# spinac.net
KiCad netlist of a schematic drawn in EAGLE
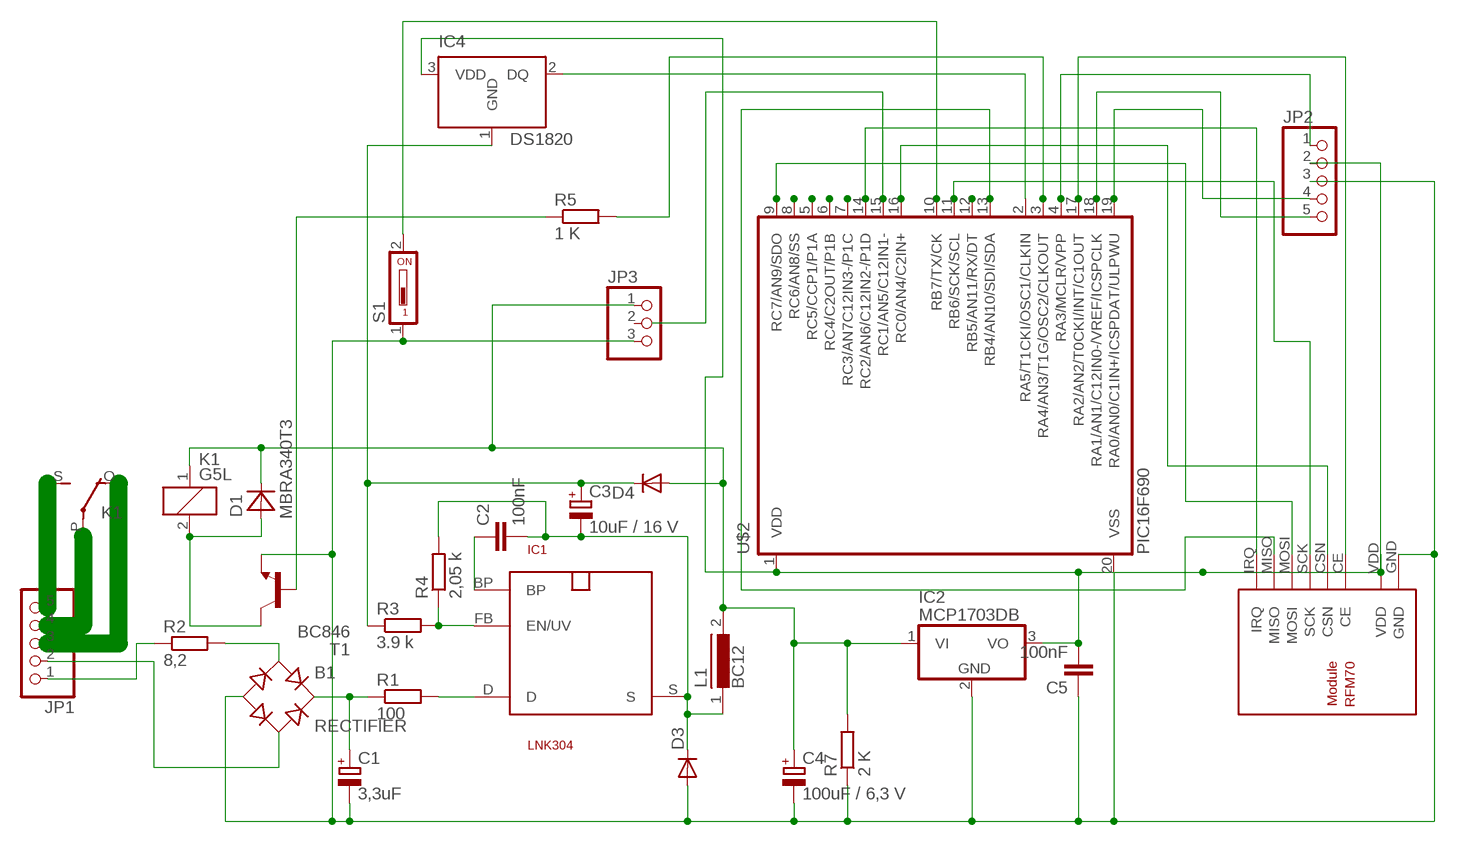
[diagram p0: schematic, sheet 1]

(export (version "E")
  (design (tool "Eeschema 10.0.6"))
  (components
    (comp (ref "B1")
      (value "RECTIFIER")
      (footprint "eagle-import:TO-269AA")
      (libsource (lib "eagle-import") (part "RECTIFIER-S40"))
    )
    (comp (ref "C1")
      (value "3,3uF")
      (footprint "eagle-import:E5-13")
      (libsource (lib "eagle-import") (part "CPOL-EUE5-13"))
    )
    (comp (ref "C2")
      (value "100nF")
      (footprint "eagle-import:C2012")
      (libsource (lib "eagle-import") (part "C-EUC2012"))
    )
    (comp (ref "C3")
      (value "10uF / 16 V")
      (footprint "eagle-import:E2,5-5")
      (libsource (lib "eagle-import") (part "CPOL-EUE2.5-5"))
    )
    (comp (ref "C4")
      (value "100uF / 6,3 V")
      (footprint "eagle-import:E2,5-5")
      (libsource (lib "eagle-import") (part "CPOL-EUE2.5-5"))
    )
    (comp (ref "C5")
      (value "100nF")
      (footprint "eagle-import:C2012")
      (libsource (lib "eagle-import") (part "C-EUC2012"))
    )
    (comp (ref "D1")
      (value "MBRA340T3")
      (footprint "eagle-import:SMA")
      (libsource (lib "eagle-import") (part "MBRA340T3"))
    )
    (comp (ref "D3")
      (value "DIODE-DO214AA")
      (footprint "eagle-import:DO214AA")
      (libsource (lib "eagle-import") (part "DIODE-DO214AA"))
    )
    (comp (ref "D4")
      (value "DIODE-DO214AA")
      (footprint "eagle-import:DO214AA")
      (libsource (lib "eagle-import") (part "DIODE-DO214AA"))
    )
    (comp (ref "IC1")
      (value "LNK304")
      (footprint "eagle-import:SO-8C")
      (libsource (lib "eagle-import") (part "SO-8C"))
    )
    (comp (ref "IC2")
      (value "MCP1703DB")
      (footprint "eagle-import:SOT223")
      (libsource (lib "eagle-import") (part "MCP1703DB"))
    )
    (comp (ref "IC4")
      (value "DS1820")
      (footprint "eagle-import:TO-92")
      (libsource (lib "eagle-import") (part "DS1820"))
    )
    (comp (ref "JP1")
      (value "PINHD-1X5")
      (footprint "eagle-import:1X05")
      (libsource (lib "eagle-import") (part "PINHD-1X5"))
    )
    (comp (ref "JP2")
      (value "PINHD-1X5")
      (footprint "eagle-import:1X05")
      (libsource (lib "eagle-import") (part "PINHD-1X5"))
    )
    (comp (ref "JP3")
      (value "PINHD-1X3")
      (footprint "eagle-import:1X03")
      (libsource (lib "eagle-import") (part "PINHD-1X3"))
    )
    (comp (ref "K1")
      (value "G5L")
      (footprint "eagle-import:G5LE")
      (libsource (lib "eagle-import") (part "G5L"))
    )
    (comp (ref "L1")
      (value "BC12")
      (footprint "eagle-import:BC12")
      (libsource (lib "eagle-import") (part "BC12"))
    )
    (comp (ref "R1")
      (value "100")
      (footprint "eagle-import:R2512W")
      (libsource (lib "eagle-import") (part "R-EU_R2512W"))
    )
    (comp (ref "R2")
      (value "8,2")
      (footprint "eagle-import:R2512W")
      (libsource (lib "eagle-import") (part "R-EU_R2512W"))
    )
    (comp (ref "R3")
      (value "3.9 k")
      (footprint "eagle-import:M2012")
      (libsource (lib "eagle-import") (part "R-EU_M2012"))
    )
    (comp (ref "R4")
      (value "2,05 k")
      (footprint "eagle-import:M2012")
      (libsource (lib "eagle-import") (part "R-EU_M2012"))
    )
    (comp (ref "R5")
      (value "1 K")
      (footprint "eagle-import:M2012")
      (libsource (lib "eagle-import") (part "R-EU_M2012"))
    )
    (comp (ref "R7")
      (value "2 K")
      (footprint "eagle-import:M2012")
      (libsource (lib "eagle-import") (part "R-EU_M2012"))
    )
    (comp (ref "S1")
      (value "SD4-01")
      (footprint "eagle-import:SD4-01")
      (libsource (lib "eagle-import") (part "SD4-01"))
    )
    (comp (ref "T1")
      (value "BC846")
      (footprint "eagle-import:SOT23")
      (libsource (lib "eagle-import") (part "BC846"))
    )
    (comp (ref "U$1")
      (value "RFM70")
      (footprint "eagle-import:RFM70")
      (libsource (lib "eagle-import") (part "RFM70"))
    )
    (comp (ref "U$2")
      (value "PIC16F690")
      (footprint "eagle-import:SSOP20")
      (libsource (lib "eagle-import") (part "PIC16F690"))
    )
  )
  (nets
    (net (code "1") (name "Net-(B1-Pad+)") (class "Default")
      (node (ref "B1") (pin "+") (pinfunction "+_+") (pintype "passive"))
      (node (ref "C1") (pin "+") (pinfunction "+_+") (pintype "passive"))
      (node (ref "R1") (pin "1") (pinfunction "1_1") (pintype "passive"))
    )
    (net (code "2") (name "Net-(B1-PadAC1)") (class "Default")
      (node (ref "B1") (pin "AC1") (pinfunction "AC1_AC1") (pintype "passive"))
      (node (ref "R2") (pin "2") (pinfunction "2_2") (pintype "passive"))
    )
    (net (code "3") (name "Net-(B1-PadAC2)") (class "Default")
      (node (ref "B1") (pin "AC2") (pinfunction "AC2_AC2") (pintype "passive"))
      (node (ref "JP1") (pin "2") (pinfunction "2_2") (pintype "passive"))
    )
    (net (code "4") (name "Net-(C2-Pad1)") (class "Default")
      (node (ref "C2") (pin "1") (pinfunction "1_1") (pintype "passive"))
      (node (ref "IC1") (pin "BP") (pinfunction "BP_BP") (pintype "passive"))
    )
    (net (code "5") (name "Net-(C2-Pad2)") (class "Default")
      (node (ref "C2") (pin "2") (pinfunction "2_2") (pintype "passive"))
      (node (ref "C3") (pin "-") (pinfunction "-_-") (pintype "passive"))
      (node (ref "D3") (pin "C") (pinfunction "C_C") (pintype "passive"))
      (node (ref "IC1") (pin "S") (pinfunction "S_S") (pintype "power_in"))
      (node (ref "L1") (pin "1") (pinfunction "1_1") (pintype "passive"))
      (node (ref "R4") (pin "2") (pinfunction "2_2") (pintype "passive"))
    )
    (net (code "6") (name "Net-(IC1-EN{slash}UV)") (class "Default")
      (node (ref "IC1") (pin "FB") (pinfunction "EN/UV_FB") (pintype "input"))
      (node (ref "R3") (pin "2") (pinfunction "2_2") (pintype "passive"))
      (node (ref "R4") (pin "1") (pinfunction "1_1") (pintype "passive"))
    )
    (net (code "7") (name "Net-(IC1-PadD)") (class "Default")
      (node (ref "IC1") (pin "D") (pinfunction "D_D") (pintype "open_collector"))
      (node (ref "R1") (pin "2") (pinfunction "2_2") (pintype "passive"))
    )
    (net (code "8") (name "Net-(IC2-GND)") (class "Default")
      (node (ref "B1") (pin "-") (pinfunction "-_-") (pintype "passive"))
      (node (ref "C1") (pin "-") (pinfunction "-_-") (pintype "passive"))
      (node (ref "C4") (pin "-") (pinfunction "-_-") (pintype "passive"))
      (node (ref "C5") (pin "1") (pinfunction "1_1") (pintype "passive"))
      (node (ref "D3") (pin "A") (pinfunction "A_A") (pintype "passive"))
      (node (ref "IC2") (pin "2") (pinfunction "GND_2") (pintype "passive"))
      (node (ref "JP2") (pin "3") (pinfunction "3_3") (pintype "passive"))
      (node (ref "JP3") (pin "3") (pinfunction "3_3") (pintype "passive"))
      (node (ref "R7") (pin "1") (pinfunction "1_1") (pintype "passive"))
      (node (ref "S1") (pin "1") (pinfunction "1_1") (pintype "passive"))
      (node (ref "T1") (pin "2") (pinfunction "E_2") (pintype "passive"))
      (node (ref "U$1") (pin "GND") (pinfunction "GND_GND") (pintype "power_in"))
      (node (ref "U$2") (pin "20") (pinfunction "VSS_20") (pintype "power_in"))
    )
    (net (code "9") (name "Net-(IC2-VI)") (class "Default")
      (node (ref "C4") (pin "+") (pinfunction "+_+") (pintype "passive"))
      (node (ref "D1") (pin "C") (pinfunction "C_C") (pintype "passive"))
      (node (ref "D4") (pin "A") (pinfunction "A_A") (pintype "passive"))
      (node (ref "IC2") (pin "1") (pinfunction "VI_1") (pintype "input"))
      (node (ref "JP3") (pin "1") (pinfunction "1_1") (pintype "passive"))
      (node (ref "K1") (pin "1") (pinfunction "1_1") (pintype "passive"))
      (node (ref "L1") (pin "2") (pinfunction "2_2") (pintype "passive"))
      (node (ref "R7") (pin "2") (pinfunction "2_2") (pintype "passive"))
    )
    (net (code "10") (name "Net-(IC2-VO)") (class "Default")
      (node (ref "C5") (pin "2") (pinfunction "2_2") (pintype "passive"))
      (node (ref "IC2") (pin "3") (pinfunction "VO_3") (pintype "passive"))
      (node (ref "IC4") (pin "3") (pinfunction "VDD_3") (pintype "input"))
      (node (ref "JP2") (pin "2") (pinfunction "2_2") (pintype "passive"))
      (node (ref "U$1") (pin "VDD") (pinfunction "VDD_VDD") (pintype "power_in"))
      (node (ref "U$2") (pin "1") (pinfunction "VDD_1") (pintype "power_in"))
    )
    (net (code "11") (name "Net-(IC4-DQ)") (class "Default")
      (node (ref "IC4") (pin "2") (pinfunction "DQ_2") (pintype "output"))
      (node (ref "U$2") (pin "2") (pinfunction "RA5/T1CKI/OSC1/CLKIN_2") (pintype "bidirectional"))
    )
    (net (code "12") (name "Net-(IC4-GND)") (class "Default")
      (node (ref "C3") (pin "+") (pinfunction "+_+") (pintype "passive"))
      (node (ref "D4") (pin "C") (pinfunction "C_C") (pintype "passive"))
      (node (ref "IC4") (pin "1") (pinfunction "GND_1") (pintype "power_in"))
      (node (ref "R3") (pin "1") (pinfunction "1_1") (pintype "passive"))
    )
    (net (code "13") (name "Net-(JP1-Pad1)") (class "Default")
      (node (ref "JP1") (pin "1") (pinfunction "1_1") (pintype "passive"))
      (node (ref "R2") (pin "1") (pinfunction "1_1") (pintype "passive"))
    )
    (net (code "14") (name "Net-(JP1-Pad3)") (class "Default")
      (node (ref "JP1") (pin "3") (pinfunction "3_3") (pintype "passive"))
      (node (ref "K1") (pin "O") (pinfunction "O_O") (pintype "passive"))
    )
    (net (code "15") (name "Net-(JP1-Pad4)") (class "Default")
      (node (ref "JP1") (pin "4") (pinfunction "4_4") (pintype "passive"))
      (node (ref "K1") (pin "P") (pinfunction "P_P") (pintype "passive"))
    )
    (net (code "16") (name "Net-(JP1-Pad5)") (class "Default")
      (node (ref "JP1") (pin "5") (pinfunction "5_5") (pintype "passive"))
      (node (ref "K1") (pin "S") (pinfunction "S_S") (pintype "passive"))
    )
    (net (code "17") (name "Net-(T1-B)") (class "Default")
      (node (ref "R5") (pin "1") (pinfunction "1_1") (pintype "passive"))
      (node (ref "T1") (pin "1") (pinfunction "B_1") (pintype "passive"))
    )
    (net (code "18") (name "Net-(T1-C)") (class "Default")
      (node (ref "D1") (pin "A") (pinfunction "A_A") (pintype "passive"))
      (node (ref "K1") (pin "2") (pinfunction "2_2") (pintype "passive"))
      (node (ref "T1") (pin "3") (pinfunction "C_3") (pintype "passive"))
    )
    (net (code "19") (name "Net-(U$2-RA0{slash}AN0{slash}C1IN+{slash}ICSPDAT{slash}ULPWU)") (class "Default")
      (node (ref "JP2") (pin "4") (pinfunction "4_4") (pintype "passive"))
      (node (ref "U$2") (pin "19") (pinfunction "RA0/AN0/C1IN+/ICSPDAT/ULPWU_19") (pintype "bidirectional"))
    )
    (net (code "20") (name "Net-(U$2-RA1{slash}AN1{slash}C12IN0-{slash}VREF{slash}ICSPCLK)") (class "Default")
      (node (ref "JP2") (pin "5") (pinfunction "5_5") (pintype "passive"))
      (node (ref "U$2") (pin "18") (pinfunction "RA1/AN1/C12IN0-/VREF/ICSPCLK_18") (pintype "bidirectional"))
    )
    (net (code "21") (name "Net-(U$2-RA2{slash}AN2{slash}T0CKI{slash}INT{slash}C1OUT)") (class "Default")
      (node (ref "U$1") (pin "CE") (pinfunction "CE_CE") (pintype "bidirectional"))
      (node (ref "U$2") (pin "17") (pinfunction "RA2/AN2/T0CKI/INT/C1OUT_17") (pintype "bidirectional"))
    )
    (net (code "22") (name "Net-(U$2-RA3{slash}MCLR{slash}VPP)") (class "Default")
      (node (ref "JP2") (pin "1") (pinfunction "1_1") (pintype "passive"))
      (node (ref "U$2") (pin "4") (pinfunction "RA3/MCLR/VPP_4") (pintype "bidirectional"))
    )
    (net (code "23") (name "Net-(U$2-RA4{slash}AN3{slash}T1G{slash}OSC2{slash}CLKOUT)") (class "Default")
      (node (ref "R5") (pin "2") (pinfunction "2_2") (pintype "passive"))
      (node (ref "U$2") (pin "3") (pinfunction "RA4/AN3/T1G/OSC2/CLKOUT_3") (pintype "bidirectional"))
    )
    (net (code "24") (name "Net-(U$2-RB4{slash}AN10{slash}SDI{slash}SDA)") (class "Default")
      (node (ref "U$1") (pin "MISO") (pinfunction "MISO_MISO") (pintype "bidirectional"))
      (node (ref "U$2") (pin "13") (pinfunction "RB4/AN10/SDI/SDA_13") (pintype "bidirectional"))
    )
    (net (code "25") (name "Net-(U$2-RB6{slash}SCK{slash}SCL)") (class "Default")
      (node (ref "U$1") (pin "SCK") (pinfunction "SCK_SCK") (pintype "bidirectional"))
      (node (ref "U$2") (pin "11") (pinfunction "RB6/SCK/SCL_11") (pintype "bidirectional"))
    )
    (net (code "26") (name "Net-(U$2-RB7{slash}TX{slash}CK)") (class "Default")
      (node (ref "S1") (pin "2") (pinfunction "2_2") (pintype "passive"))
      (node (ref "U$2") (pin "10") (pinfunction "RB7/TX/CK_10") (pintype "bidirectional"))
    )
    (net (code "27") (name "Net-(U$2-RC0{slash}AN4{slash}C2IN+)") (class "Default")
      (node (ref "U$1") (pin "CSN") (pinfunction "CSN_CSN") (pintype "bidirectional"))
      (node (ref "U$2") (pin "16") (pinfunction "RC0/AN4/C2IN+_16") (pintype "bidirectional"))
    )
    (net (code "28") (name "Net-(U$2-RC2{slash}AN6{slash}C12IN2-{slash}P1D)") (class "Default")
      (node (ref "U$1") (pin "IRQ") (pinfunction "IRQ_IRQ") (pintype "bidirectional"))
      (node (ref "U$2") (pin "14") (pinfunction "RC2/AN6/C12IN2-/P1D_14") (pintype "bidirectional"))
    )
    (net (code "29") (name "Net-(U$2-RC7{slash}AN9{slash}SDO)") (class "Default")
      (node (ref "U$1") (pin "MOSI") (pinfunction "MOSI_MOSI") (pintype "bidirectional"))
      (node (ref "U$2") (pin "9") (pinfunction "RC7/AN9/SDO_9") (pintype "bidirectional"))
    )
    (net (code "30") (name "unconnected-(JP3-Pad2)") (class "Default")
      (node (ref "JP3") (pin "2") (pinfunction "2_2") (pintype "passive"))
    )
    (net (code "31") (name "unconnected-(U$2-RB5{slash}AN11{slash}RX{slash}DT-Pad12)") (class "Default")
      (node (ref "U$2") (pin "12") (pinfunction "RB5/AN11/RX/DT_12") (pintype "bidirectional"))
    )
    (net (code "32") (name "unconnected-(U$2-RC1{slash}AN5{slash}C12IN1--Pad15)") (class "Default")
      (node (ref "U$2") (pin "15") (pinfunction "RC1/AN5/C12IN1-_15") (pintype "bidirectional"))
    )
    (net (code "33") (name "unconnected-(U$2-RC3{slash}AN7C12IN3-{slash}P1C-Pad7)") (class "Default")
      (node (ref "U$2") (pin "7") (pinfunction "RC3/AN7C12IN3-/P1C_7") (pintype "bidirectional"))
    )
    (net (code "34") (name "unconnected-(U$2-RC4{slash}C2OUT{slash}P1B-Pad6)") (class "Default")
      (node (ref "U$2") (pin "6") (pinfunction "RC4/C2OUT/P1B_6") (pintype "bidirectional"))
    )
    (net (code "35") (name "unconnected-(U$2-RC5{slash}CCP1{slash}P1A-Pad5)") (class "Default")
      (node (ref "U$2") (pin "5") (pinfunction "RC5/CCP1/P1A_5") (pintype "bidirectional"))
    )
    (net (code "36") (name "unconnected-(U$2-RC6{slash}AN8{slash}SS-Pad8)") (class "Default")
      (node (ref "U$2") (pin "8") (pinfunction "RC6/AN8/SS_8") (pintype "bidirectional"))
    )
  )
)
